# ultrasonic.net
KiCad netlist of a schematic drawn in EAGLE
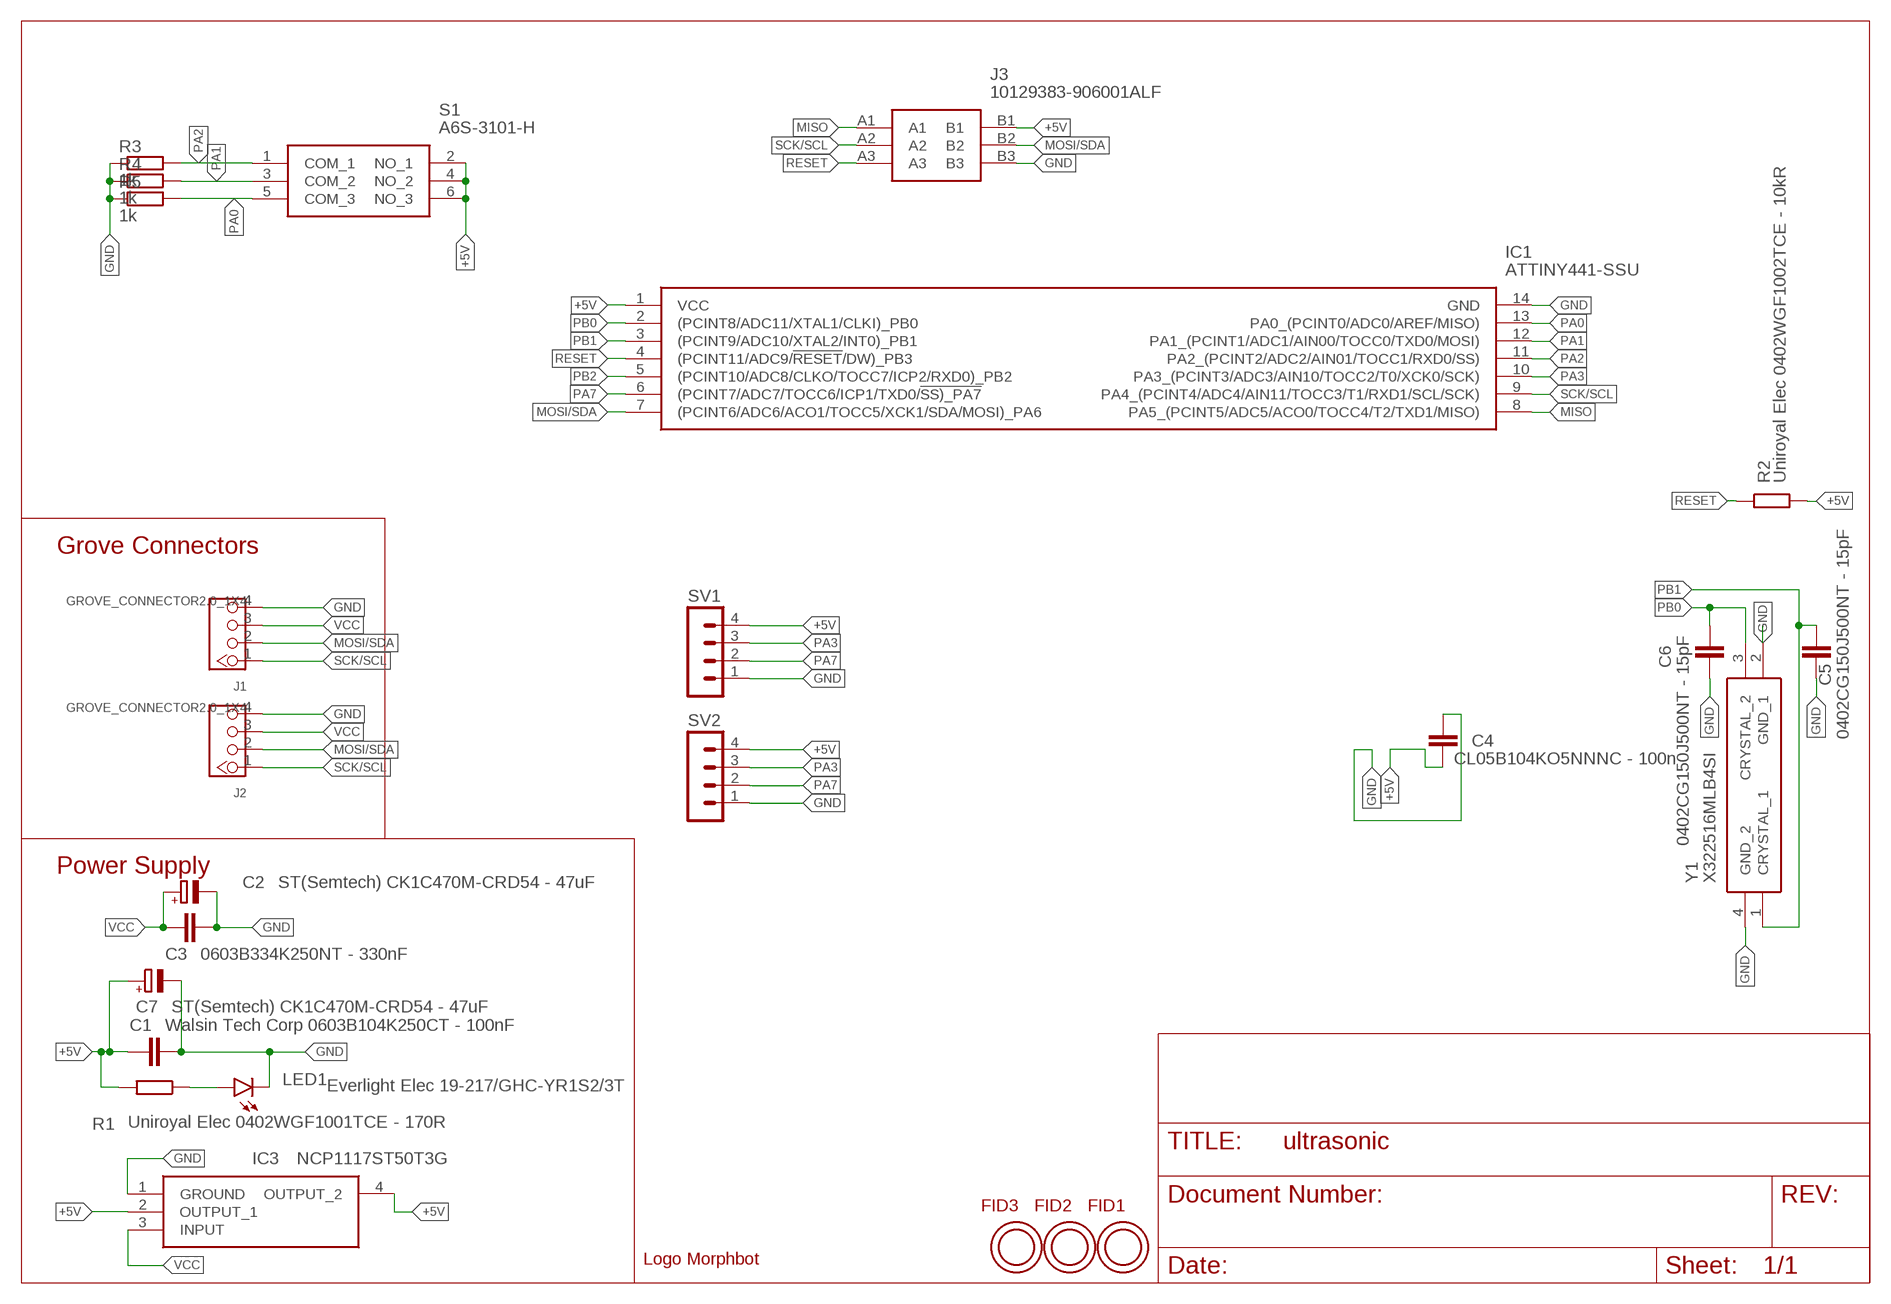
[diagram p0: schematic, sheet 1]

(export (version "E")
  (design (tool "Eeschema 10.0.6"))
  (components
    (comp (ref "C1")
      (value "Walsin Tech Corp 0603B104K250CT - 100nF")
      (footprint "eagle-import:C0603")
      (libsource (lib "eagle-import") (part "C-EUC0603"))
    )
    (comp (ref "C2")
      (value "ST(Semtech) CK1C470M-CRD54 - 47uF")
      (footprint "eagle-import:PANASONIC_C")
      (libsource (lib "eagle-import") (part "CPOL-EUC"))
    )
    (comp (ref "C3")
      (value "0603B334K250NT - 330nF")
      (footprint "eagle-import:C0603")
      (libsource (lib "eagle-import") (part "C-EUC0603"))
    )
    (comp (ref "C4")
      (value "CL05B104KO5NNNC - 100n")
      (footprint "eagle-import:C0402")
      (libsource (lib "eagle-import") (part "C-EUC0402"))
    )
    (comp (ref "C5")
      (value "0402CG150J500NT - 15pF")
      (footprint "eagle-import:C0402")
      (libsource (lib "eagle-import") (part "C-EUC0402"))
    )
    (comp (ref "C6")
      (value "0402CG150J500NT - 15pF")
      (footprint "eagle-import:C0402")
      (libsource (lib "eagle-import") (part "C-EUC0402"))
    )
    (comp (ref "C7")
      (value "ST(Semtech) CK1C470M-CRD54 - 47uF")
      (footprint "eagle-import:PANASONIC_C")
      (libsource (lib "eagle-import") (part "CPOL-EUC"))
    )
    (comp (ref "FID1")
      (value "OPEN-PNP-FIDUCIAL")
      (footprint "eagle-import:OPEN-PNP-FIDUCIAL")
      (libsource (lib "eagle-import") (part "OPEN-PNP-FIDUCIAL"))
    )
    (comp (ref "FID2")
      (value "OPEN-PNP-FIDUCIAL")
      (footprint "eagle-import:OPEN-PNP-FIDUCIAL")
      (libsource (lib "eagle-import") (part "OPEN-PNP-FIDUCIAL"))
    )
    (comp (ref "FID3")
      (value "OPEN-PNP-FIDUCIAL")
      (footprint "eagle-import:OPEN-PNP-FIDUCIAL")
      (libsource (lib "eagle-import") (part "OPEN-PNP-FIDUCIAL"))
    )
    (comp (ref "IC1")
      (value "ATTINY441-SSU")
      (footprint "eagle-import:SOIC127P600X175-14N")
      (fields (field (name "MOUSER_PART_NUMBER") "556-ATTINY441-SSU"))
      (libsource (lib "eagle-import") (part "ATTINY441-SSU"))
    )
    (comp (ref "IC3")
      (value "NCP1117ST50T3G")
      (footprint "eagle-import:SOT230P700X180-4N")
      (fields (field (name "MOUSER_PART_NUMBER") "863-NCP1117ST50T3G"))
      (libsource (lib "eagle-import") (part "NCP1117ST50T3G"))
    )
    (comp (ref "J1")
      (value "GROVE_CONNECTOR2.0_1X4")
      (footprint "eagle-import:2.0_1X4_STRAIGHT")
      (libsource (lib "eagle-import") (part "GROVE_CONNECTOR2.0_1X4"))
    )
    (comp (ref "J2")
      (value "GROVE_CONNECTOR2.0_1X4")
      (footprint "eagle-import:2.0_1X4_STRAIGHT")
      (libsource (lib "eagle-import") (part "GROVE_CONNECTOR2.0_1X4"))
    )
    (comp (ref "J3")
      (value "10129383-906001ALF")
      (footprint "eagle-import:10129383906001ALF")
      (fields (field (name "MOUSER_PART_NUMBER") "649-1012938390601ALF"))
      (libsource (lib "eagle-import") (part "10129383-906001ALF"))
    )
    (comp (ref "LED1")
      (value "Everlight Elec 19-217/GHC-YR1S2/3T")
      (footprint "eagle-import:CHIPLED_0603")
      (libsource (lib "eagle-import") (part "LEDCHIPLED_0603"))
    )
    (comp (ref "R1")
      (value "Uniroyal Elec 0402WGF1001TCE - 170R")
      (footprint "eagle-import:R0402")
      (libsource (lib "eagle-import") (part "R-EU_R0402"))
    )
    (comp (ref "R2")
      (value "Uniroyal Elec 0402WGF1002TCE - 10kR")
      (footprint "eagle-import:R0402")
      (libsource (lib "eagle-import") (part "R-EU_R0402"))
    )
    (comp (ref "R3")
      (value "1k")
      (footprint "eagle-import:R0402")
      (libsource (lib "eagle-import") (part "R-EU_R0402"))
    )
    (comp (ref "R4")
      (value "1k")
      (footprint "eagle-import:R0402")
      (libsource (lib "eagle-import") (part "R-EU_R0402"))
    )
    (comp (ref "R5")
      (value "1k")
      (footprint "eagle-import:R0402")
      (libsource (lib "eagle-import") (part "R-EU_R0402"))
    )
    (comp (ref "S1")
      (value "A6S-3101-H")
      (footprint "eagle-import:A6S3104H")
      (fields (field (name "MOUSER_PART_NUMBER") "653-A6S-3101-H"))
      (libsource (lib "eagle-import") (part "A6S-3101-H"))
    )
    (comp (ref "SV1")
      (value "MA04-1")
      (footprint "eagle-import:MA04-1")
      (libsource (lib "eagle-import") (part "MA04-1"))
    )
    (comp (ref "SV2")
      (value "MA04-1")
      (footprint "eagle-import:MA04-1")
      (libsource (lib "eagle-import") (part "MA04-1"))
    )
    (comp (ref "U$1")
      (value "LOGO_MORPHBOT5MM")
      (footprint "eagle-import:LOGO_MORPHBOT")
      (libsource (lib "eagle-import") (part "LOGO_MORPHBOT5MM"))
    )
    (comp (ref "Y1")
      (value "X322516MLB4SI")
      (footprint "eagle-import:X322516MLB4SI")
      (libsource (lib "eagle-import") (part "X322516MLB4SI"))
    )
  )
  (nets
    (net (code "1") (name "+5V") (class "Default")
      (node (ref "C1") (pin "1") (pinfunction "1_1") (pintype "passive"))
      (node (ref "C4") (pin "1") (pinfunction "1_1") (pintype "passive"))
      (node (ref "C7") (pin "+") (pinfunction "+_+") (pintype "passive"))
      (node (ref "IC1") (pin "1") (pinfunction "VCC_1") (pintype "bidirectional"))
      (node (ref "IC3") (pin "2") (pinfunction "OUTPUT_1_2") (pintype "bidirectional"))
      (node (ref "IC3") (pin "4") (pinfunction "OUTPUT_2_4") (pintype "bidirectional"))
      (node (ref "J3") (pin "B1") (pinfunction "B1_B1") (pintype "bidirectional"))
      (node (ref "R1") (pin "2") (pinfunction "2_2") (pintype "passive"))
      (node (ref "R2") (pin "2") (pinfunction "2_2") (pintype "passive"))
      (node (ref "S1") (pin "2") (pinfunction "NO_1_2") (pintype "bidirectional"))
      (node (ref "S1") (pin "4") (pinfunction "NO_2_4") (pintype "bidirectional"))
      (node (ref "S1") (pin "6") (pinfunction "NO_3_6") (pintype "bidirectional"))
      (node (ref "SV1") (pin "4") (pinfunction "4_4") (pintype "passive"))
      (node (ref "SV2") (pin "4") (pinfunction "4_4") (pintype "passive"))
    )
    (net (code "2") (name "GND") (class "Default")
      (node (ref "C1") (pin "2") (pinfunction "2_2") (pintype "passive"))
      (node (ref "C2") (pin "-") (pinfunction "-_-") (pintype "passive"))
      (node (ref "C3") (pin "1") (pinfunction "1_1") (pintype "passive"))
      (node (ref "C4") (pin "2") (pinfunction "2_2") (pintype "passive"))
      (node (ref "C5") (pin "1") (pinfunction "1_1") (pintype "passive"))
      (node (ref "C6") (pin "1") (pinfunction "1_1") (pintype "passive"))
      (node (ref "C7") (pin "-") (pinfunction "-_-") (pintype "passive"))
      (node (ref "IC1") (pin "14") (pinfunction "GND_14") (pintype "bidirectional"))
      (node (ref "IC3") (pin "1") (pinfunction "GROUND_1") (pintype "bidirectional"))
      (node (ref "J1") (pin "4") (pinfunction "4_4") (pintype "bidirectional"))
      (node (ref "J2") (pin "4") (pinfunction "4_4") (pintype "bidirectional"))
      (node (ref "J3") (pin "B3") (pinfunction "B3_B3") (pintype "bidirectional"))
      (node (ref "LED1") (pin "C") (pinfunction "C_C") (pintype "passive"))
      (node (ref "R3") (pin "1") (pinfunction "1_1") (pintype "passive"))
      (node (ref "R4") (pin "1") (pinfunction "1_1") (pintype "passive"))
      (node (ref "R5") (pin "1") (pinfunction "1_1") (pintype "passive"))
      (node (ref "SV1") (pin "1") (pinfunction "1_1") (pintype "passive"))
      (node (ref "SV2") (pin "1") (pinfunction "1_1") (pintype "passive"))
      (node (ref "Y1") (pin "2") (pinfunction "GND_1_2") (pintype "bidirectional"))
      (node (ref "Y1") (pin "4") (pinfunction "GND_2_4") (pintype "bidirectional"))
    )
    (net (code "3") (name "MISO") (class "Default")
      (node (ref "IC1") (pin "8") (pinfunction "PA5_(PCINT5/ADC5/ACO0/TOCC4/T2/TXD1/MISO)_8") (pintype "bidirectional"))
      (node (ref "J3") (pin "A1") (pinfunction "A1_A1") (pintype "bidirectional"))
    )
    (net (code "4") (name "MOSI{slash}SDA") (class "Default")
      (node (ref "IC1") (pin "7") (pinfunction "(PCINT6/ADC6/ACO1/TOCC5/XCK1/SDA/MOSI)_PA6_7") (pintype "bidirectional"))
      (node (ref "J1") (pin "2") (pinfunction "2_2") (pintype "bidirectional"))
      (node (ref "J2") (pin "2") (pinfunction "2_2") (pintype "bidirectional"))
      (node (ref "J3") (pin "B2") (pinfunction "B2_B2") (pintype "bidirectional"))
    )
    (net (code "5") (name "Net-(LED1-PadA)") (class "Default")
      (node (ref "LED1") (pin "A") (pinfunction "A_A") (pintype "passive"))
      (node (ref "R1") (pin "1") (pinfunction "1_1") (pintype "passive"))
    )
    (net (code "6") (name "PA0") (class "Default")
      (node (ref "IC1") (pin "13") (pinfunction "PA0_(PCINT0/ADC0/AREF/MISO)_13") (pintype "bidirectional"))
      (node (ref "R5") (pin "2") (pinfunction "2_2") (pintype "passive"))
      (node (ref "S1") (pin "5") (pinfunction "COM_3_5") (pintype "bidirectional"))
    )
    (net (code "7") (name "PA1") (class "Default")
      (node (ref "IC1") (pin "12") (pinfunction "PA1_(PCINT1/ADC1/AIN00/TOCC0/TXD0/MOSI)_12") (pintype "bidirectional"))
      (node (ref "R4") (pin "2") (pinfunction "2_2") (pintype "passive"))
      (node (ref "S1") (pin "3") (pinfunction "COM_2_3") (pintype "bidirectional"))
    )
    (net (code "8") (name "PA2") (class "Default")
      (node (ref "IC1") (pin "11") (pinfunction "PA2_(PCINT2/ADC2/AIN01/TOCC1/RXD0/SS)_11") (pintype "bidirectional"))
      (node (ref "R3") (pin "2") (pinfunction "2_2") (pintype "passive"))
      (node (ref "S1") (pin "1") (pinfunction "COM_1_1") (pintype "bidirectional"))
    )
    (net (code "9") (name "PA3") (class "Default")
      (node (ref "IC1") (pin "10") (pinfunction "PA3_(PCINT3/ADC3/AIN10/TOCC2/T0/XCK0/SCK)_10") (pintype "bidirectional"))
      (node (ref "SV1") (pin "3") (pinfunction "3_3") (pintype "passive"))
      (node (ref "SV2") (pin "3") (pinfunction "3_3") (pintype "passive"))
    )
    (net (code "10") (name "PA7") (class "Default")
      (node (ref "IC1") (pin "6") (pinfunction "(PCINT7/ADC7/TOCC6/ICP1/TXD0/~{SS})_PA7_6") (pintype "bidirectional"))
      (node (ref "SV1") (pin "2") (pinfunction "2_2") (pintype "passive"))
      (node (ref "SV2") (pin "2") (pinfunction "2_2") (pintype "passive"))
    )
    (net (code "11") (name "PB0") (class "Default")
      (node (ref "C6") (pin "2") (pinfunction "2_2") (pintype "passive"))
      (node (ref "IC1") (pin "2") (pinfunction "(PCINT8/ADC11/XTAL1/CLKI)_PB0_2") (pintype "bidirectional"))
      (node (ref "Y1") (pin "3") (pinfunction "CRYSTAL_2_3") (pintype "bidirectional"))
    )
    (net (code "12") (name "PB1") (class "Default")
      (node (ref "C5") (pin "2") (pinfunction "2_2") (pintype "passive"))
      (node (ref "IC1") (pin "3") (pinfunction "(PCINT9/ADC10/XTAL2/INT0)_PB1_3") (pintype "bidirectional"))
      (node (ref "Y1") (pin "1") (pinfunction "CRYSTAL_1_1") (pintype "bidirectional"))
    )
    (net (code "13") (name "PB2") (class "Default")
      (node (ref "IC1") (pin "5") (pinfunction "(PCINT10/ADC8/CLKO/TOCC7/ICP2/RXD0)_PB2_5") (pintype "bidirectional"))
    )
    (net (code "14") (name "RESET") (class "Default")
      (node (ref "IC1") (pin "4") (pinfunction "(PCINT11/ADC9/~{RESET}/DW)_PB3_4") (pintype "bidirectional"))
      (node (ref "J3") (pin "A3") (pinfunction "A3_A3") (pintype "bidirectional"))
      (node (ref "R2") (pin "1") (pinfunction "1_1") (pintype "passive"))
    )
    (net (code "15") (name "SCK{slash}SCL") (class "Default")
      (node (ref "IC1") (pin "9") (pinfunction "PA4_(PCINT4/ADC4/AIN11/TOCC3/T1/RXD1/SCL/SCK)_9") (pintype "bidirectional"))
      (node (ref "J1") (pin "1") (pinfunction "1_1") (pintype "bidirectional"))
      (node (ref "J2") (pin "1") (pinfunction "1_1") (pintype "bidirectional"))
      (node (ref "J3") (pin "A2") (pinfunction "A2_A2") (pintype "bidirectional"))
    )
    (net (code "16") (name "VCC") (class "Default")
      (node (ref "C2") (pin "+") (pinfunction "+_+") (pintype "passive"))
      (node (ref "C3") (pin "2") (pinfunction "2_2") (pintype "passive"))
      (node (ref "IC3") (pin "3") (pinfunction "INPUT_3") (pintype "bidirectional"))
      (node (ref "J1") (pin "3") (pinfunction "3_3") (pintype "bidirectional"))
      (node (ref "J2") (pin "3") (pinfunction "3_3") (pintype "bidirectional"))
    )
  )
)
